# HackCard.net
KiCad netlist of a schematic drawn in EasyEDA
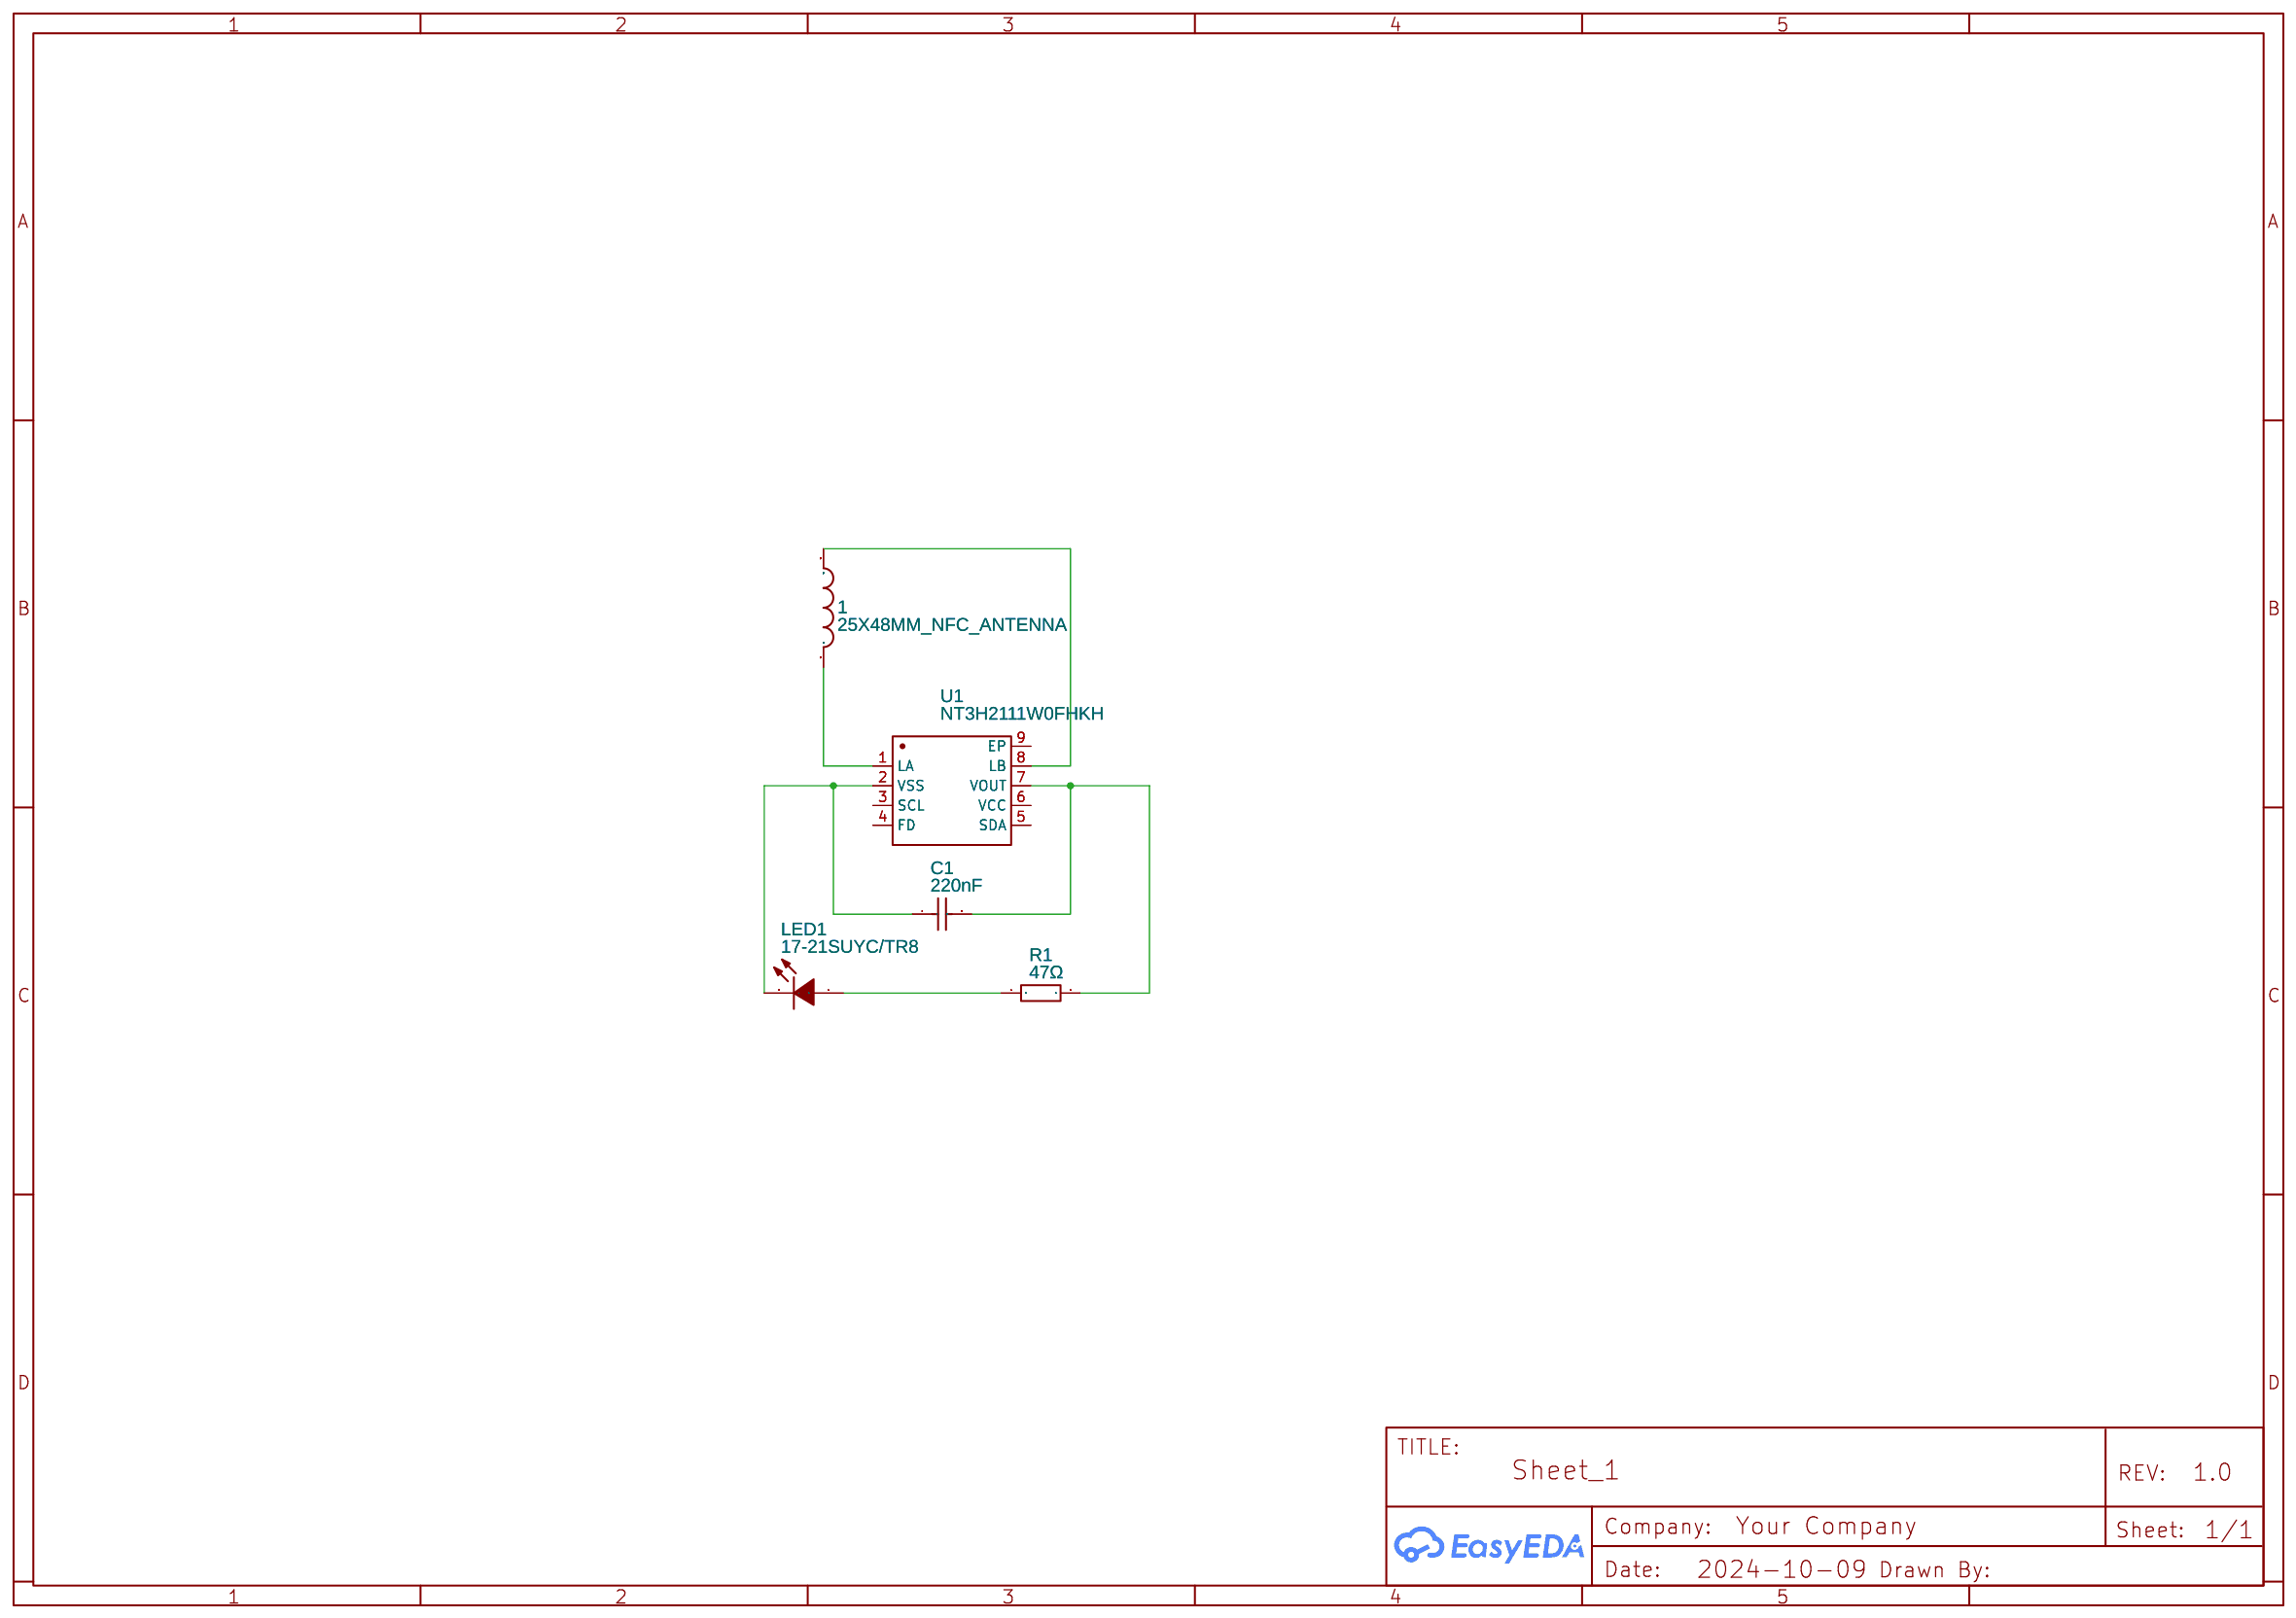
[diagram p0: schematic sheet]

(export (version "E")
  (design (tool "Eeschema 10.0.6"))
  (components
    (comp (ref "1") (value "25X48MM_NFC_ANTENNA") (libsource (lib "") (part "25X48MM_NFC_ANTENNA")))
    (comp (ref "C1")
      (value "220nF")
      (fields
        (field (name "Manufacturer Part") "CL10B224KA8NNNC")
        (field (name "Manufacturer") "SAMSUNG(三星)")
      )
      (libsource (lib "") (part "CL10B224KA8NNNC"))
    )
    (comp (ref "LED1")
      (value "17-21SUYC/TR8")
      (fields (field (name "Manufacturer Part") "KT-0805黄灯") (field (name "Manufacturer") "KENTO"))
      (libsource (lib "") (part "17-21SUYC/TR8"))
    )
    (comp (ref "R1")
      (value "47Ω")
      (fields
        (field (name "Manufacturer Part") "0603WAF470JT5E")
        (field (name "Manufacturer") "UNI-ROYAL(厚声)")
      )
      (libsource (lib "") (part "0603WAF470JT5E"))
    )
    (comp (ref "U1")
      (value "NT3H2111W0FHKH")
      (fields (field (name "Manufacturer") "NXP(恩智浦)"))
      (libsource (lib "") (part "NT3H2111W0FHKH"))
    )
  )
  (nets
    (net (code "1") (name "Net-(LED1-+)") (class "Default")
      (node (ref "LED1") (pin "1") (pinfunction "+_1") (pintype "unspecified"))
      (node (ref "R1") (pin "1") (pinfunction "1_1") (pintype "input"))
    )
    (net (code "2") (name "Net-(LED1--)") (class "Default")
      (node (ref "C1") (pin "1") (pinfunction "1_1") (pintype "input"))
      (node (ref "LED1") (pin "2") (pinfunction "-_2") (pintype "unspecified"))
      (node (ref "U1") (pin "2") (pinfunction "VSS_2") (pintype "unspecified"))
    )
    (net (code "3") (name "Net-(U1-LA)") (class "Default")
      (node (ref "1") (pin "P$2") (pinfunction "P$2_P$2") (pintype "bidirectional"))
      (node (ref "U1") (pin "1") (pinfunction "LA_1") (pintype "unspecified"))
    )
    (net (code "4") (name "Net-(U1-LB)") (class "Default")
      (node (ref "1") (pin "P$1") (pinfunction "P$1_P$1") (pintype "bidirectional"))
      (node (ref "U1") (pin "8") (pinfunction "LB_8") (pintype "unspecified"))
    )
    (net (code "5") (name "Net-(U1-VOUT)") (class "Default")
      (node (ref "C1") (pin "2") (pinfunction "2_2") (pintype "input"))
      (node (ref "R1") (pin "2") (pinfunction "2_2") (pintype "input"))
      (node (ref "U1") (pin "7") (pinfunction "VOUT_7") (pintype "unspecified"))
    )
    (net (code "6") (name "unconnected-(U1-EP-Pad9)") (class "Default")
      (node (ref "U1") (pin "9") (pinfunction "EP_9") (pintype "unspecified"))
    )
    (net (code "7") (name "unconnected-(U1-FD-Pad4)") (class "Default")
      (node (ref "U1") (pin "4") (pinfunction "FD_4") (pintype "unspecified"))
    )
    (net (code "8") (name "unconnected-(U1-SCL-Pad3)") (class "Default")
      (node (ref "U1") (pin "3") (pinfunction "SCL_3") (pintype "unspecified"))
    )
    (net (code "9") (name "unconnected-(U1-SDA-Pad5)") (class "Default")
      (node (ref "U1") (pin "5") (pinfunction "SDA_5") (pintype "unspecified"))
    )
    (net (code "10") (name "unconnected-(U1-VCC-Pad6)") (class "Default")
      (node (ref "U1") (pin "6") (pinfunction "VCC_6") (pintype "unspecified"))
    )
  )
)
